# main_board.net
KiCad netlist of a schematic drawn in EAGLE
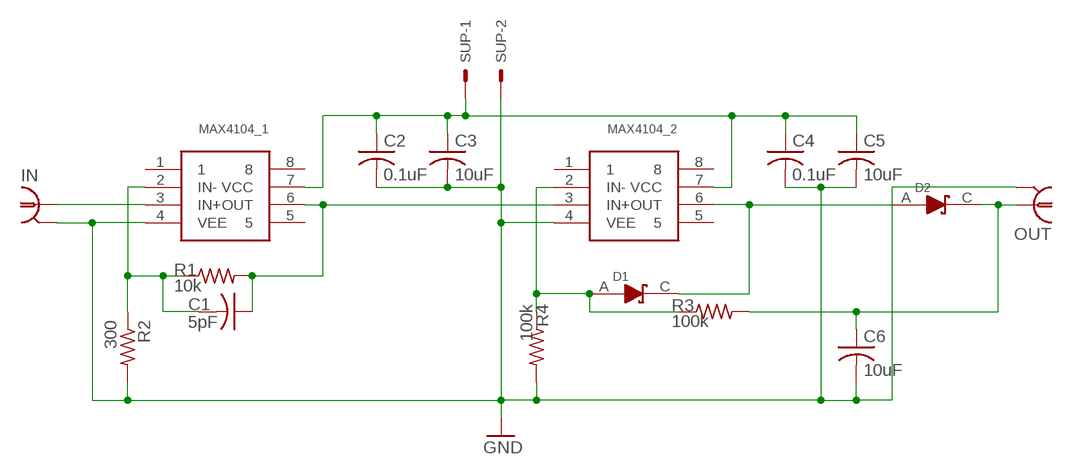
[diagram p0: schematic, sheet 1]

(export (version "E")
  (design (tool "Eeschema 10.0.6"))
  (components
    (comp (ref "C1")
      (value "5pF")
      (footprint "eagle-import:C0805")
      (libsource (lib "eagle-import") (part "C-USC0805"))
    )
    (comp (ref "C2")
      (value "0.1uF")
      (footprint "eagle-import:C0805")
      (libsource (lib "eagle-import") (part "C-USC0805"))
    )
    (comp (ref "C3")
      (value "10uF")
      (footprint "eagle-import:C0805")
      (libsource (lib "eagle-import") (part "C-USC0805"))
    )
    (comp (ref "C4")
      (value "0.1uF")
      (footprint "eagle-import:C0805")
      (libsource (lib "eagle-import") (part "C-USC0805"))
    )
    (comp (ref "C5")
      (value "10uF")
      (footprint "eagle-import:C0805")
      (libsource (lib "eagle-import") (part "C-USC0805"))
    )
    (comp (ref "C6")
      (value "10uF")
      (footprint "eagle-import:C0805")
      (libsource (lib "eagle-import") (part "C-USC0805"))
    )
    (comp (ref "D1")
      (value "SCH_D1")
      (footprint "eagle-import:SML0805")
      (libsource (lib "eagle-import") (part "SCH_D1"))
    )
    (comp (ref "D2")
      (value "SCH_D1")
      (footprint "eagle-import:SML0805")
      (libsource (lib "eagle-import") (part "SCH_D1"))
    )
    (comp (ref "IN")
      (value "LTI-SASF54GT")
      (footprint "eagle-import:LTI-SASF54GT")
      (libsource (lib "eagle-import") (part "LTI-SASF54GT"))
    )
    (comp (ref "MAX4104_1")
      (value "MAX4104")
      (footprint "eagle-import:SO8")
      (libsource (lib "eagle-import") (part "MAX4104"))
    )
    (comp (ref "MAX4104_2")
      (value "MAX4104")
      (footprint "eagle-import:SO8")
      (libsource (lib "eagle-import") (part "MAX4104"))
    )
    (comp (ref "OUT")
      (value "LTI-SASF54GT")
      (footprint "eagle-import:LTI-SASF54GT")
      (libsource (lib "eagle-import") (part "LTI-SASF54GT"))
    )
    (comp (ref "R1")
      (value "10k")
      (footprint "eagle-import:M0805")
      (libsource (lib "eagle-import") (part "R-US_M0805"))
    )
    (comp (ref "R2")
      (value "300")
      (footprint "eagle-import:M0805")
      (libsource (lib "eagle-import") (part "R-US_M0805"))
    )
    (comp (ref "R3")
      (value "100k")
      (footprint "eagle-import:M0805")
      (libsource (lib "eagle-import") (part "R-US_M0805"))
    )
    (comp (ref "R4")
      (value "100k")
      (footprint "eagle-import:M0805")
      (libsource (lib "eagle-import") (part "R-US_M0805"))
    )
    (comp (ref "SUP")
      (value "332-02")
      (footprint "eagle-import:332-02")
      (libsource (lib "eagle-import") (part "332-02"))
    )
  )
  (nets
    (net (code "1") (name "GND") (class "Default")
      (node (ref "C2") (pin "2") (pinfunction "2_2") (pintype "passive"))
      (node (ref "C3") (pin "2") (pinfunction "2_2") (pintype "passive"))
      (node (ref "C4") (pin "2") (pinfunction "2_2") (pintype "passive"))
      (node (ref "C5") (pin "2") (pinfunction "2_2") (pintype "passive"))
      (node (ref "C6") (pin "2") (pinfunction "2_2") (pintype "passive"))
      (node (ref "IN") (pin "2") (pinfunction "2_2") (pintype "passive"))
      (node (ref "IN") (pin "3") (pinfunction "2_3") (pintype "passive"))
      (node (ref "IN") (pin "4") (pinfunction "2_4") (pintype "passive"))
      (node (ref "IN") (pin "5") (pinfunction "2_5") (pintype "passive"))
      (node (ref "MAX4104_1") (pin "4") (pinfunction "VEE_4") (pintype "power_in"))
      (node (ref "MAX4104_2") (pin "4") (pinfunction "VEE_4") (pintype "power_in"))
      (node (ref "OUT") (pin "2") (pinfunction "2_2") (pintype "passive"))
      (node (ref "OUT") (pin "3") (pinfunction "2_3") (pintype "passive"))
      (node (ref "OUT") (pin "4") (pinfunction "2_4") (pintype "passive"))
      (node (ref "OUT") (pin "5") (pinfunction "2_5") (pintype "passive"))
      (node (ref "R2") (pin "2") (pinfunction "2_2") (pintype "passive"))
      (node (ref "R4") (pin "2") (pinfunction "2_2") (pintype "passive"))
      (node (ref "SUP") (pin "2") (pinfunction "S_2") (pintype "passive"))
    )
    (net (code "2") (name "Net-(D1-IN)") (class "Default")
      (node (ref "D1") (pin "A") (pinfunction "IN_A") (pintype "input"))
      (node (ref "MAX4104_2") (pin "2") (pinfunction "IN-_2") (pintype "input"))
      (node (ref "R3") (pin "1") (pinfunction "1_1") (pintype "passive"))
      (node (ref "R4") (pin "1") (pinfunction "1_1") (pintype "passive"))
    )
    (net (code "3") (name "Net-(D1-OUT)") (class "Default")
      (node (ref "D1") (pin "C") (pinfunction "OUT_C") (pintype "output"))
      (node (ref "D2") (pin "A") (pinfunction "IN_A") (pintype "input"))
      (node (ref "MAX4104_2") (pin "6") (pinfunction "OUT_6") (pintype "output"))
    )
    (net (code "4") (name "Net-(D2-OUT)") (class "Default")
      (node (ref "C6") (pin "1") (pinfunction "1_1") (pintype "passive"))
      (node (ref "D2") (pin "C") (pinfunction "OUT_C") (pintype "output"))
      (node (ref "OUT") (pin "1") (pinfunction "1_1") (pintype "passive"))
      (node (ref "R3") (pin "2") (pinfunction "2_2") (pintype "passive"))
    )
    (net (code "5") (name "Net-(MAX4104_1-IN+)") (class "Default")
      (node (ref "IN") (pin "1") (pinfunction "1_1") (pintype "passive"))
      (node (ref "MAX4104_1") (pin "3") (pinfunction "IN+_3") (pintype "input"))
    )
    (net (code "6") (name "Net-(MAX4104_1-IN-)") (class "Default")
      (node (ref "C1") (pin "2") (pinfunction "2_2") (pintype "passive"))
      (node (ref "MAX4104_1") (pin "2") (pinfunction "IN-_2") (pintype "input"))
      (node (ref "R1") (pin "1") (pinfunction "1_1") (pintype "passive"))
      (node (ref "R2") (pin "1") (pinfunction "1_1") (pintype "passive"))
    )
    (net (code "7") (name "Net-(MAX4104_1-OUT)") (class "Default")
      (node (ref "C1") (pin "1") (pinfunction "1_1") (pintype "passive"))
      (node (ref "MAX4104_1") (pin "6") (pinfunction "OUT_6") (pintype "output"))
      (node (ref "MAX4104_2") (pin "3") (pinfunction "IN+_3") (pintype "input"))
      (node (ref "R1") (pin "2") (pinfunction "2_2") (pintype "passive"))
    )
    (net (code "8") (name "Net-(MAX4104_1-VCC)") (class "Default")
      (node (ref "C2") (pin "1") (pinfunction "1_1") (pintype "passive"))
      (node (ref "C3") (pin "1") (pinfunction "1_1") (pintype "passive"))
      (node (ref "C4") (pin "1") (pinfunction "1_1") (pintype "passive"))
      (node (ref "C5") (pin "1") (pinfunction "1_1") (pintype "passive"))
      (node (ref "MAX4104_1") (pin "7") (pinfunction "VCC_7") (pintype "power_in"))
      (node (ref "MAX4104_2") (pin "7") (pinfunction "VCC_7") (pintype "power_in"))
      (node (ref "SUP") (pin "1") (pinfunction "S_1") (pintype "passive"))
    )
    (net (code "9") (name "unconnected-(MAX4104_1-Pad1)") (class "Default")
      (node (ref "MAX4104_1") (pin "1") (pinfunction "1_1") (pintype "no_connect"))
    )
    (net (code "10") (name "unconnected-(MAX4104_1-Pad5)") (class "Default")
      (node (ref "MAX4104_1") (pin "5") (pinfunction "5_5") (pintype "no_connect"))
    )
    (net (code "11") (name "unconnected-(MAX4104_1-Pad8)") (class "Default")
      (node (ref "MAX4104_1") (pin "8") (pinfunction "8_8") (pintype "no_connect"))
    )
    (net (code "12") (name "unconnected-(MAX4104_2-Pad1)") (class "Default")
      (node (ref "MAX4104_2") (pin "1") (pinfunction "1_1") (pintype "no_connect"))
    )
    (net (code "13") (name "unconnected-(MAX4104_2-Pad5)") (class "Default")
      (node (ref "MAX4104_2") (pin "5") (pinfunction "5_5") (pintype "no_connect"))
    )
    (net (code "14") (name "unconnected-(MAX4104_2-Pad8)") (class "Default")
      (node (ref "MAX4104_2") (pin "8") (pinfunction "8_8") (pintype "no_connect"))
    )
  )
)
